# User_Switch.net
KiCad netlist of a schematic drawn in Altium Designer
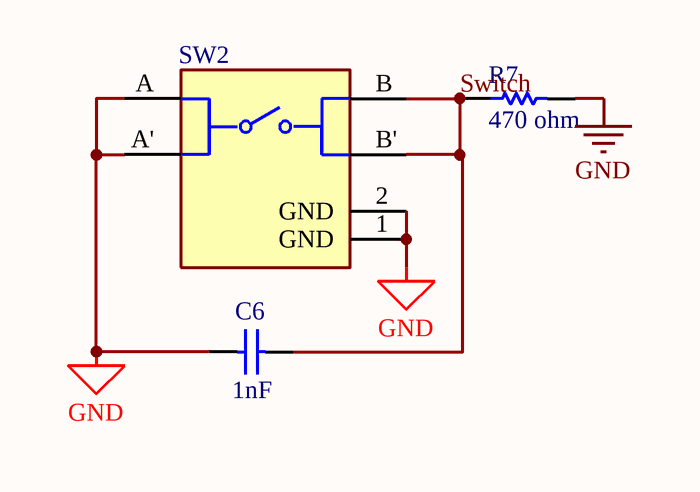
[diagram p0: User Switch.SchDoc]

(export (version "E")
  (design (tool "Eeschema 10.0.6"))
  (components
    (comp (ref "C6")
      (value "VJ0805D102KXAAJ")
      (footprint "CAPC2013X145X48LL20T23")
      (fields (field (name "MANUFACTURER") "Vitramon") (field (name "PARAMETER 1") "1nF"))
      (libsource (lib "Altium Content Vault") (part "CAP"))
    )
    (comp (ref "R7")
      (value "CRCW0805470RFKEA")
      (footprint "RESC2013X50X30LL20T20")
      (fields (field (name "MANUFACTURER") "Vishay Dale") (field (name "PARAMETER 1") "470 ohm"))
      (libsource (lib "Altium Content Vault") (part "RES"))
    )
    (comp (ref "SW2")
      (value "EVQ-PLMA15")
      (footprint "FP-EVQ-PLMA15-MFG")
      (description "SWITCH TACTILE SPST-NO 0.02A 15V")
      (fields
        (field (name "OCTOPART") "https://octopart.com/evq-plma15-panasonic-39850235")
        (field (name "MANUFACTURER") "Panasonic Electronic Components")
      )
      (libsource (lib "Altium Content Vault") (part "fc7b47d2e4813f0909612a6c4f63938"))
    )
  )
  (nets
    (net (code "1") (name "/Switch") (class "Default")
      (node (ref "C6") (pin "2") (pinfunction "2_2") (pintype "passive"))
      (node (ref "R7") (pin "1") (pinfunction "1_1") (pintype "passive"))
      (node (ref "SW2") (pin "B") (pinfunction "B_B") (pintype "passive"))
      (node (ref "SW2") (pin "B'") (pinfunction "B'_B'") (pintype "passive"))
    )
    (net (code "2") (name "GND") (class "Default")
      (node (ref "C6") (pin "1") (pinfunction "1_1") (pintype "passive"))
      (node (ref "R7") (pin "2") (pinfunction "2_2") (pintype "passive"))
      (node (ref "SW2") (pin "1") (pinfunction "GND_1") (pintype "power_in"))
      (node (ref "SW2") (pin "2") (pinfunction "GND_2") (pintype "power_in"))
      (node (ref "SW2") (pin "A") (pinfunction "A_A") (pintype "passive"))
      (node (ref "SW2") (pin "A'") (pinfunction "A'_A'") (pintype "passive"))
    )
  )
)
